# Connector_Sheet2.net
KiCad netlist of a schematic drawn in Altium Designer
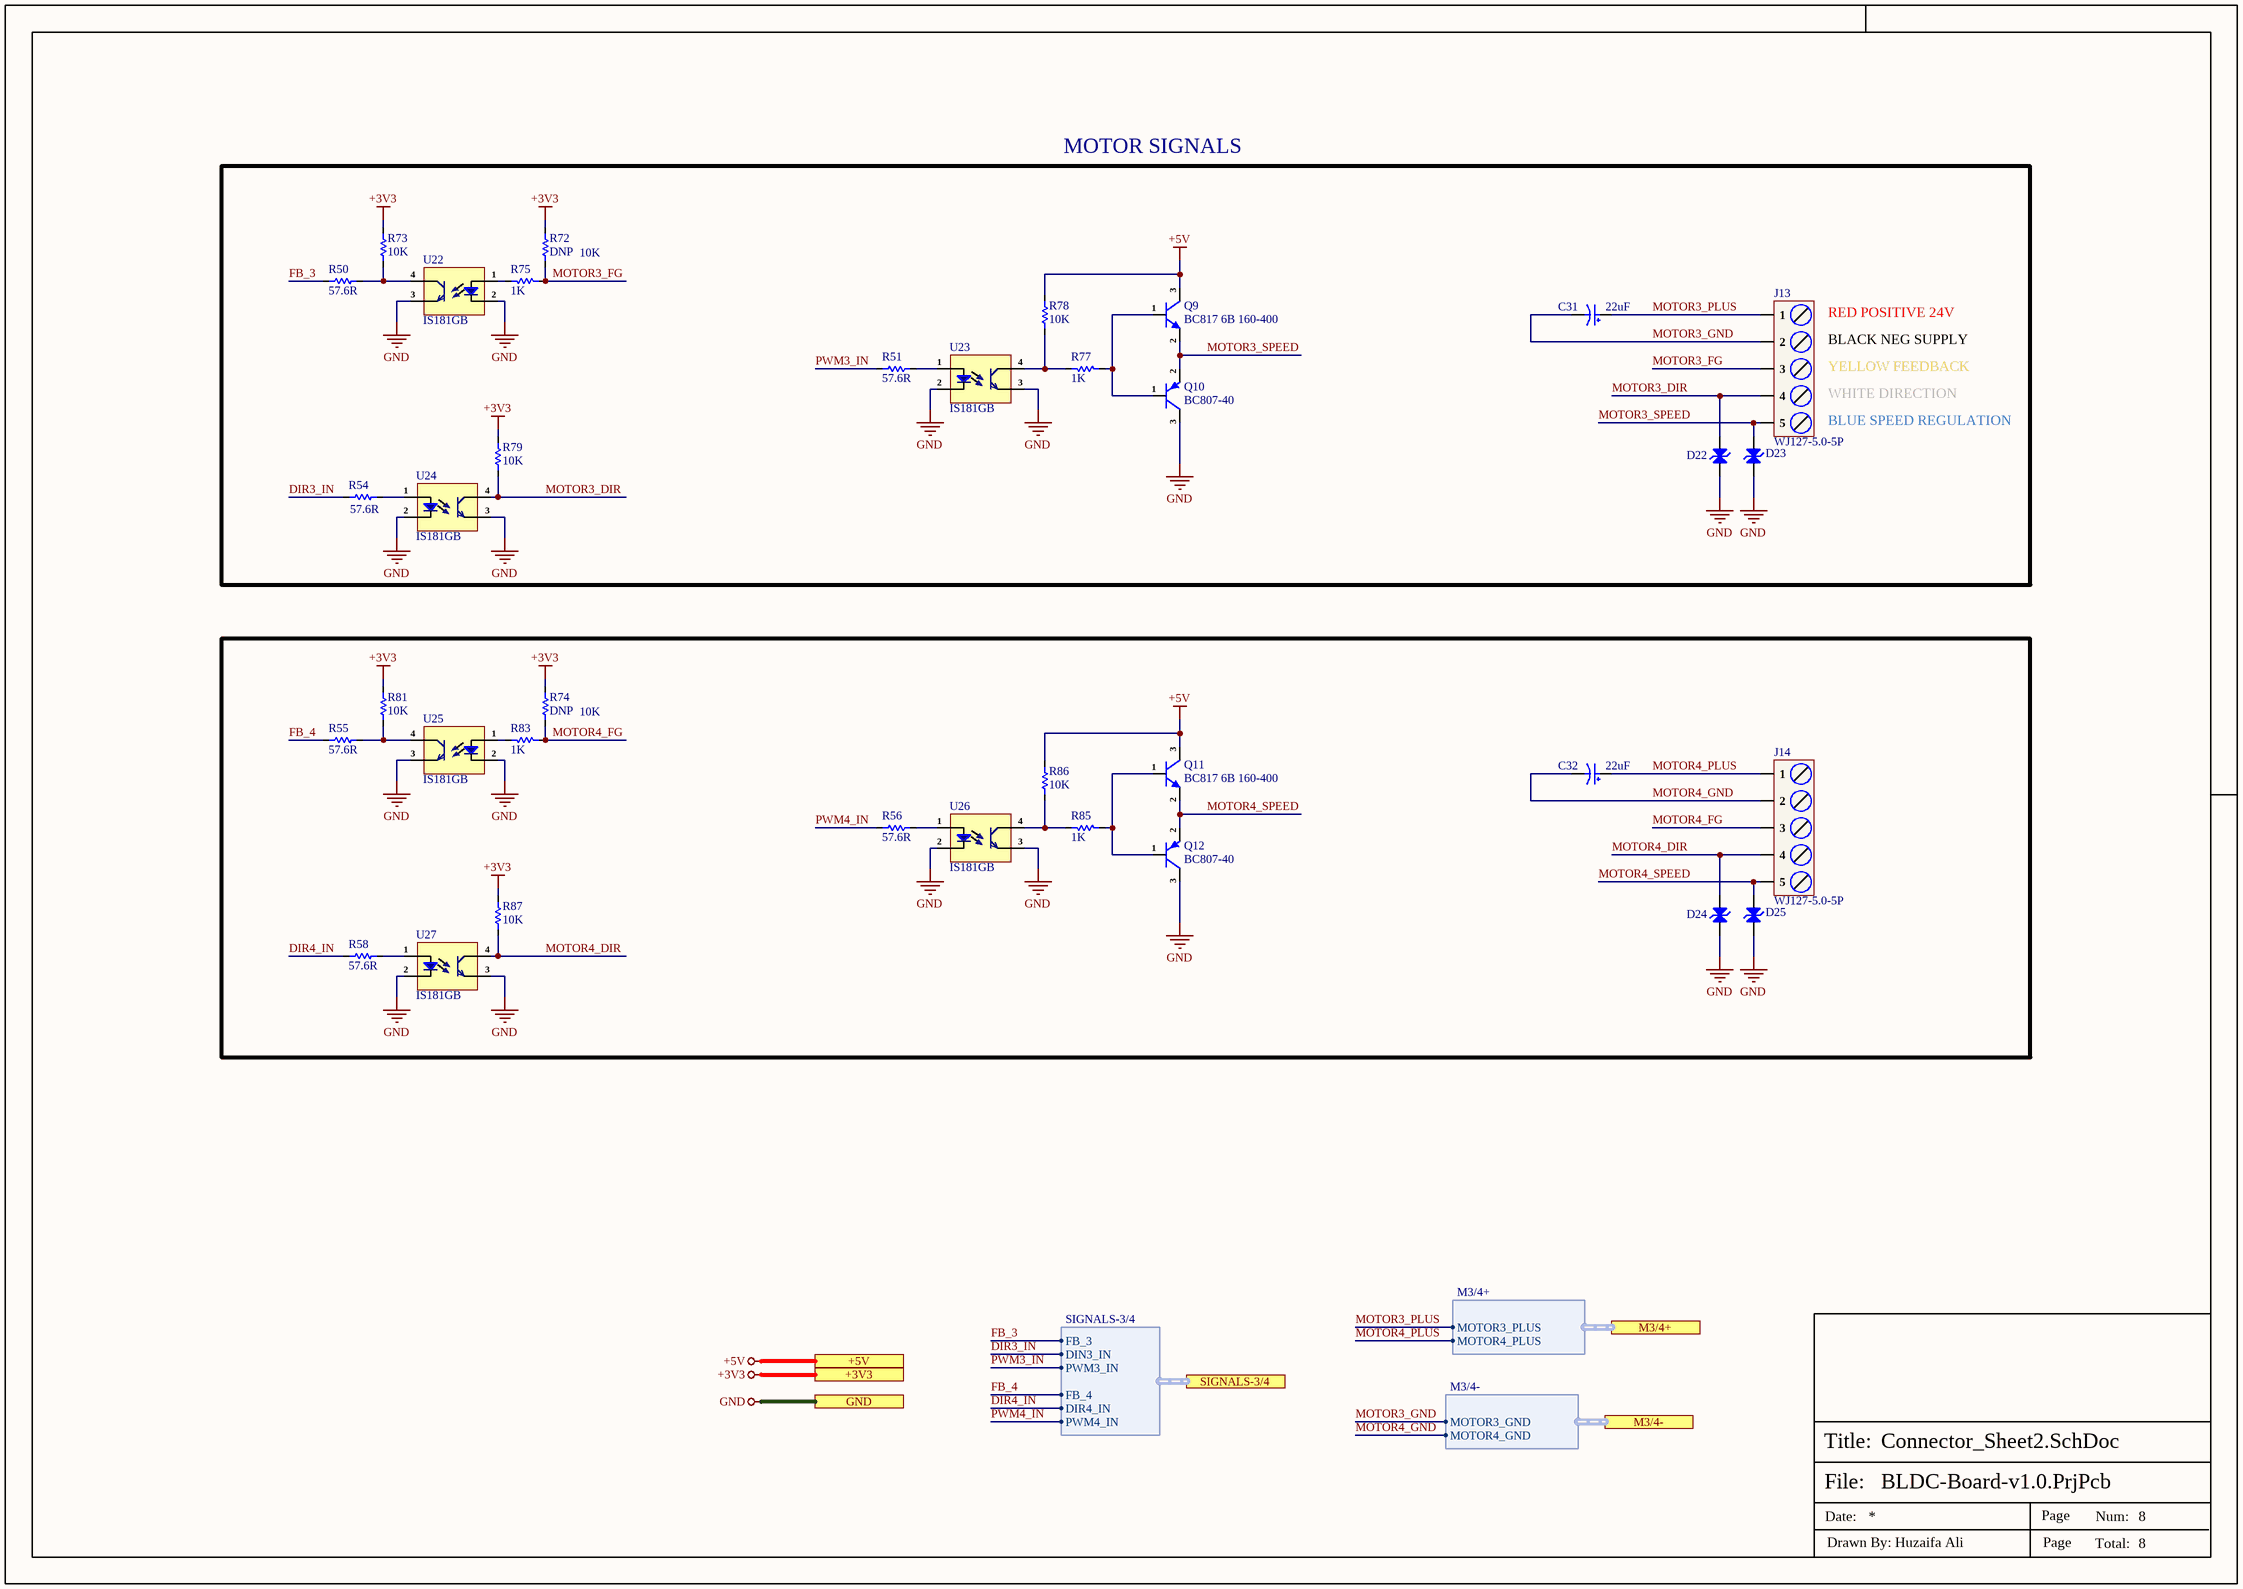
[diagram p0: Connector_Sheet2.SchDoc]

(export (version "E")
  (design (tool "Eeschema 10.0.6"))
  (components
    (comp (ref "C31")
      (value "22uF")
      (footprint "VKMD1652D220MV")
      (description "22uF 200V 320mA@100kHz ±20% SMD,D8xL16.5mm Aluminum Electrolytic Capacitors - SMD ROHS")
      (fields (field (name "MANUFACTURER") "Ymin") (field (name "MANUFACTURER PART NUMBER") "VKMD1652D220MV"))
      (libsource (lib "eSpark Libraries") (part "VKMD1652D220MV"))
    )
    (comp (ref "C32")
      (value "22uF")
      (footprint "VKMD1652D220MV")
      (description "22uF 200V 320mA@100kHz ±20% SMD,D8xL16.5mm Aluminum Electrolytic Capacitors - SMD ROHS")
      (fields (field (name "MANUFACTURER") "Ymin") (field (name "MANUFACTURER PART NUMBER") "VKMD1652D220MV"))
      (libsource (lib "eSpark Libraries") (part "VKMD1652D220MV"))
    )
    (comp (ref "D22")
      (value "ESD5B5.0ST1G")
      (footprint "SOD-523")
      (description "TVS DIODE 5VWM SOD523")
      (fields (field (name "MANUFACTURER") "ON Semiconductor") (field (name "LCSC PART NUMBER") "C93623"))
      (libsource (lib "eSpark Libraries") (part "ESD5B5.0ST1G"))
    )
    (comp (ref "D23")
      (value "ESD5B5.0ST1G")
      (footprint "SOD-523")
      (description "TVS DIODE 5VWM SOD523")
      (fields (field (name "MANUFACTURER") "ON Semiconductor") (field (name "LCSC PART NUMBER") "C93623"))
      (libsource (lib "eSpark Libraries") (part "ESD5B5.0ST1G"))
    )
    (comp (ref "D24")
      (value "ESD5B5.0ST1G")
      (footprint "SOD-523")
      (description "TVS DIODE 5VWM SOD523")
      (fields (field (name "MANUFACTURER") "ON Semiconductor") (field (name "LCSC PART NUMBER") "C93623"))
      (libsource (lib "eSpark Libraries") (part "ESD5B5.0ST1G"))
    )
    (comp (ref "D25")
      (value "ESD5B5.0ST1G")
      (footprint "SOD-523")
      (description "TVS DIODE 5VWM SOD523")
      (fields (field (name "MANUFACTURER") "ON Semiconductor") (field (name "LCSC PART NUMBER") "C93623"))
      (libsource (lib "eSpark Libraries") (part "ESD5B5.0ST1G"))
    )
    (comp (ref "J13")
      (value "WJ127-5.0-5P")
      (footprint "WJ127-5.0-5P")
      (description "1x5P -40℃~+105℃ 15A 250V Green 14~26 Straight pin 5mm 1.5 1 5 Plugin,P=5mm Screw terminal ROHS")
      (fields (field (name "MANUFACTURER") "Ningbo Kangnex Elec") (field (name "LCSC PART NUMBER") "C192780"))
      (libsource (lib "eSpark Libraries") (part "WJ127-5.0-5P"))
    )
    (comp (ref "J14")
      (value "WJ127-5.0-5P")
      (footprint "WJ127-5.0-5P")
      (description "1x5P -40℃~+105℃ 15A 250V Green 14~26 Straight pin 5mm 1.5 1 5 Plugin,P=5mm Screw terminal ROHS")
      (fields (field (name "MANUFACTURER") "Ningbo Kangnex Elec") (field (name "LCSC PART NUMBER") "C192780"))
      (libsource (lib "eSpark Libraries") (part "WJ127-5.0-5P"))
    )
    (comp (ref "Q9")
      (value "BC817 6B 160-400")
      (footprint "SOT-23")
      (description "45V 300mW 100@100mA,1V 500mA NPN SOT-23 Bipolar Transistors - BJT ROHS")
      (fields (field (name "MANUFACTURER") "DOWO") (field (name "LCSC PART NUMBER") "C371086"))
      (libsource (lib "eSpark Libraries") (part "BC817 6B 160-400"))
    )
    (comp (ref "Q10")
      (value "BC807-40")
      (footprint "SOT-23")
      (description "45V 310mW 250@100mA,1V 800mA SOT-23 Bipolar (BJT) ROHS")
      (fields (field (name "MANUFACTURER") "KEXIN") (field (name "LCSC PART NUMBER") "C489159"))
      (libsource (lib "eSpark Libraries") (part "BC807-40"))
    )
    (comp (ref "Q11")
      (value "BC817 6B 160-400")
      (footprint "SOT-23")
      (description "45V 300mW 100@100mA,1V 500mA NPN SOT-23 Bipolar Transistors - BJT ROHS")
      (fields (field (name "MANUFACTURER") "DOWO") (field (name "LCSC PART NUMBER") "C371086"))
      (libsource (lib "eSpark Libraries") (part "BC817 6B 160-400"))
    )
    (comp (ref "Q12")
      (value "BC807-40")
      (footprint "SOT-23")
      (description "45V 310mW 250@100mA,1V 800mA SOT-23 Bipolar (BJT) ROHS")
      (fields (field (name "MANUFACTURER") "KEXIN") (field (name "LCSC PART NUMBER") "C489159"))
      (libsource (lib "eSpark Libraries") (part "BC807-40"))
    )
    (comp (ref "R50")
      (value "57.6R")
      (footprint "Res-0402")
      (description "RES SMD 57.6 OHM 1% 1/10W 0402")
      (fields
        (field (name "MANUFACTURER") "Panasonic")
        (field (name "MANUFACTURER PART NUMBER") "ERJ-2RKF57R6X")
      )
      (libsource (lib "eSpark Libraries") (part "ERJ-2RKF57R6X"))
    )
    (comp (ref "R51")
      (value "57.6R")
      (footprint "Res-0402")
      (description "RES SMD 57.6 OHM 1% 1/10W 0402")
      (fields
        (field (name "MANUFACTURER") "Panasonic")
        (field (name "MANUFACTURER PART NUMBER") "ERJ-2RKF57R6X")
      )
      (libsource (lib "eSpark Libraries") (part "ERJ-2RKF57R6X"))
    )
    (comp (ref "R54")
      (value "57.6R")
      (footprint "Res-0402")
      (description "RES SMD 57.6 OHM 1% 1/10W 0402")
      (fields
        (field (name "MANUFACTURER") "Panasonic")
        (field (name "MANUFACTURER PART NUMBER") "ERJ-2RKF57R6X")
      )
      (libsource (lib "eSpark Libraries") (part "ERJ-2RKF57R6X"))
    )
    (comp (ref "R55")
      (value "57.6R")
      (footprint "Res-0402")
      (description "RES SMD 57.6 OHM 1% 1/10W 0402")
      (fields
        (field (name "MANUFACTURER") "Panasonic")
        (field (name "MANUFACTURER PART NUMBER") "ERJ-2RKF57R6X")
      )
      (libsource (lib "eSpark Libraries") (part "ERJ-2RKF57R6X"))
    )
    (comp (ref "R56")
      (value "57.6R")
      (footprint "Res-0402")
      (description "RES SMD 57.6 OHM 1% 1/10W 0402")
      (fields
        (field (name "MANUFACTURER") "Panasonic")
        (field (name "MANUFACTURER PART NUMBER") "ERJ-2RKF57R6X")
      )
      (libsource (lib "eSpark Libraries") (part "ERJ-2RKF57R6X"))
    )
    (comp (ref "R58")
      (value "57.6R")
      (footprint "Res-0402")
      (description "RES SMD 57.6 OHM 1% 1/10W 0402")
      (fields
        (field (name "MANUFACTURER") "Panasonic")
        (field (name "MANUFACTURER PART NUMBER") "ERJ-2RKF57R6X")
      )
      (libsource (lib "eSpark Libraries") (part "ERJ-2RKF57R6X"))
    )
    (comp (ref "R72")
      (value "DNP")
      (footprint "Res-0402")
      (description "RES 10K OHM 1% 1/16W 0402")
      (fields
        (field (name "MANUFACTURER") "Yageo")
        (field (name "MANUFACTURER PART NUMBER") "RC0402FR-0710KL")
      )
      (libsource (lib "eSpark Libraries") (part "RC0402FR-0710KL"))
    )
    (comp (ref "R73")
      (value "10K")
      (footprint "Res-0402")
      (description "RES 10K OHM 1% 1/16W 0402")
      (fields
        (field (name "MANUFACTURER") "Yageo")
        (field (name "MANUFACTURER PART NUMBER") "RC0402FR-0710KL")
      )
      (libsource (lib "eSpark Libraries") (part "RC0402FR-0710KL"))
    )
    (comp (ref "R74")
      (value "DNP")
      (footprint "Res-0402")
      (description "RES 10K OHM 1% 1/16W 0402")
      (fields
        (field (name "MANUFACTURER") "Yageo")
        (field (name "MANUFACTURER PART NUMBER") "RC0402FR-0710KL")
      )
      (libsource (lib "eSpark Libraries") (part "RC0402FR-0710KL"))
    )
    (comp (ref "R75")
      (value "1K")
      (footprint "Res-0402")
      (description "RES SMD 1K OHM 1% 1/5W 0402")
      (fields
        (field (name "MANUFACTURER") "Vishay Dale")
        (field (name "MANUFACTURER PART NUMBER") "CRCW04021K00FKEDHP")
      )
      (libsource (lib "eSpark Libraries") (part "CRCW04021K00FKEDHP"))
    )
    (comp (ref "R77")
      (value "1K")
      (footprint "Res-0402")
      (description "RES SMD 1K OHM 1% 1/5W 0402")
      (fields
        (field (name "MANUFACTURER") "Vishay Dale")
        (field (name "MANUFACTURER PART NUMBER") "CRCW04021K00FKEDHP")
      )
      (libsource (lib "eSpark Libraries") (part "CRCW04021K00FKEDHP"))
    )
    (comp (ref "R78")
      (value "10K")
      (footprint "Res-0402")
      (description "RES 10K OHM 1% 1/16W 0402")
      (fields
        (field (name "MANUFACTURER") "Yageo")
        (field (name "MANUFACTURER PART NUMBER") "RC0402FR-0710KL")
      )
      (libsource (lib "eSpark Libraries") (part "RC0402FR-0710KL"))
    )
    (comp (ref "R79")
      (value "10K")
      (footprint "Res-0402")
      (description "RES 10K OHM 1% 1/16W 0402")
      (fields
        (field (name "MANUFACTURER") "Yageo")
        (field (name "MANUFACTURER PART NUMBER") "RC0402FR-0710KL")
      )
      (libsource (lib "eSpark Libraries") (part "RC0402FR-0710KL"))
    )
    (comp (ref "R81")
      (value "10K")
      (footprint "Res-0402")
      (description "RES 10K OHM 1% 1/16W 0402")
      (fields
        (field (name "MANUFACTURER") "Yageo")
        (field (name "MANUFACTURER PART NUMBER") "RC0402FR-0710KL")
      )
      (libsource (lib "eSpark Libraries") (part "RC0402FR-0710KL"))
    )
    (comp (ref "R83")
      (value "1K")
      (footprint "Res-0402")
      (description "RES SMD 1K OHM 1% 1/5W 0402")
      (fields
        (field (name "MANUFACTURER") "Vishay Dale")
        (field (name "MANUFACTURER PART NUMBER") "CRCW04021K00FKEDHP")
      )
      (libsource (lib "eSpark Libraries") (part "CRCW04021K00FKEDHP"))
    )
    (comp (ref "R85")
      (value "1K")
      (footprint "Res-0402")
      (description "RES SMD 1K OHM 1% 1/5W 0402")
      (fields
        (field (name "MANUFACTURER") "Vishay Dale")
        (field (name "MANUFACTURER PART NUMBER") "CRCW04021K00FKEDHP")
      )
      (libsource (lib "eSpark Libraries") (part "CRCW04021K00FKEDHP"))
    )
    (comp (ref "R86")
      (value "10K")
      (footprint "Res-0402")
      (description "RES 10K OHM 1% 1/16W 0402")
      (fields
        (field (name "MANUFACTURER") "Yageo")
        (field (name "MANUFACTURER PART NUMBER") "RC0402FR-0710KL")
      )
      (libsource (lib "eSpark Libraries") (part "RC0402FR-0710KL"))
    )
    (comp (ref "R87")
      (value "10K")
      (footprint "Res-0402")
      (description "RES 10K OHM 1% 1/16W 0402")
      (fields
        (field (name "MANUFACTURER") "Yageo")
        (field (name "MANUFACTURER PART NUMBER") "RC0402FR-0710KL")
      )
      (libsource (lib "eSpark Libraries") (part "RC0402FR-0710KL"))
    )
    (comp (ref "U22")
      (value "IS181GB")
      (footprint "SOP-4_2.54")
      (description "Optoisolator Transistor Output 3750Vrms 1 Channel")
      (fields (field (name "MANUFACTURER") "Isocom") (field (name "LCSC PART NUMBER") "C84196"))
      (libsource (lib "eSpark Libraries") (part "IS181GB"))
    )
    (comp (ref "U23")
      (value "IS181GB")
      (footprint "SOP-4_2.54")
      (description "Optoisolator Transistor Output 3750Vrms 1 Channel")
      (fields (field (name "MANUFACTURER") "Isocom") (field (name "LCSC PART NUMBER") "C84196"))
      (libsource (lib "") (part "IS181GB_1"))
    )
    (comp (ref "U24")
      (value "IS181GB")
      (footprint "SOP-4_2.54")
      (description "Optoisolator Transistor Output 3750Vrms 1 Channel")
      (fields (field (name "MANUFACTURER") "Isocom") (field (name "LCSC PART NUMBER") "C84196"))
      (libsource (lib "") (part "IS181GB_1"))
    )
    (comp (ref "U25")
      (value "IS181GB")
      (footprint "SOP-4_2.54")
      (description "Optoisolator Transistor Output 3750Vrms 1 Channel")
      (fields (field (name "MANUFACTURER") "Isocom") (field (name "LCSC PART NUMBER") "C84196"))
      (libsource (lib "eSpark Libraries") (part "IS181GB"))
    )
    (comp (ref "U26")
      (value "IS181GB")
      (footprint "SOP-4_2.54")
      (description "Optoisolator Transistor Output 3750Vrms 1 Channel")
      (fields (field (name "MANUFACTURER") "Isocom") (field (name "LCSC PART NUMBER") "C84196"))
      (libsource (lib "") (part "IS181GB_1"))
    )
    (comp (ref "U27")
      (value "IS181GB")
      (footprint "SOP-4_2.54")
      (description "Optoisolator Transistor Output 3750Vrms 1 Channel")
      (fields (field (name "MANUFACTURER") "Isocom") (field (name "LCSC PART NUMBER") "C84196"))
      (libsource (lib "") (part "IS181GB_1"))
    )
  )
  (nets
    (net (code "4") (name "+3V3") (class "Default")
      (node (ref "R72") (pin "2") (pinfunction "2_2") (pintype "passive"))
      (node (ref "R73") (pin "2") (pinfunction "2_2") (pintype "passive"))
      (node (ref "R74") (pin "2") (pinfunction "2_2") (pintype "passive"))
      (node (ref "R79") (pin "2") (pinfunction "2_2") (pintype "passive"))
      (node (ref "R81") (pin "2") (pinfunction "2_2") (pintype "passive"))
      (node (ref "R87") (pin "2") (pinfunction "2_2") (pintype "passive"))
    )
    (net (code "5") (name "+5V") (class "Default")
      (node (ref "Q11") (pin "3") (pinfunction "C_3") (pintype "passive"))
      (node (ref "Q9") (pin "3") (pinfunction "C_3") (pintype "passive"))
      (node (ref "R78") (pin "1") (pinfunction "1_1") (pintype "passive"))
      (node (ref "R86") (pin "1") (pinfunction "1_1") (pintype "passive"))
    )
    (net (code "6") (name "/DIR3_IN") (class "Default")
      (node (ref "R54") (pin "1") (pinfunction "1_1") (pintype "passive"))
    )
    (net (code "7") (name "/DIR4_IN") (class "Default")
      (node (ref "R58") (pin "1") (pinfunction "1_1") (pintype "passive"))
    )
    (net (code "8") (name "/FB_3") (class "Default")
      (node (ref "R50") (pin "1") (pinfunction "1_1") (pintype "passive"))
    )
    (net (code "9") (name "/FB_4") (class "Default")
      (node (ref "R55") (pin "1") (pinfunction "1_1") (pintype "passive"))
    )
    (net (code "10") (name "/MOTOR3_DIR") (class "Default")
      (node (ref "D22") (pin "2") (pinfunction "A_2") (pintype "passive"))
      (node (ref "J13") (pin "4") (pinfunction "4_4") (pintype "passive"))
      (node (ref "R79") (pin "1") (pinfunction "1_1") (pintype "passive"))
      (node (ref "U24") (pin "4") (pinfunction "C_4") (pintype "passive"))
    )
    (net (code "11") (name "/MOTOR3_FG") (class "Default")
      (node (ref "J13") (pin "3") (pinfunction "3_3") (pintype "passive"))
      (node (ref "R72") (pin "1") (pinfunction "1_1") (pintype "passive"))
      (node (ref "R75") (pin "1") (pinfunction "1_1") (pintype "passive"))
    )
    (net (code "12") (name "/MOTOR3_GND") (class "Default")
      (node (ref "C31") (pin "2") (pintype "passive"))
      (node (ref "J13") (pin "2") (pinfunction "2_2") (pintype "passive"))
    )
    (net (code "13") (name "/MOTOR3_PLUS") (class "Default")
      (node (ref "C31") (pin "1") (pintype "passive"))
      (node (ref "J13") (pin "1") (pinfunction "1_1") (pintype "passive"))
    )
    (net (code "14") (name "/MOTOR3_SPEED") (class "Default")
      (node (ref "D23") (pin "2") (pinfunction "A_2") (pintype "passive"))
      (node (ref "J13") (pin "5") (pinfunction "5_5") (pintype "passive"))
      (node (ref "Q10") (pin "2") (pinfunction "E_2") (pintype "passive"))
      (node (ref "Q9") (pin "2") (pinfunction "E_2") (pintype "passive"))
    )
    (net (code "15") (name "/MOTOR4_DIR") (class "Default")
      (node (ref "D24") (pin "2") (pinfunction "A_2") (pintype "passive"))
      (node (ref "J14") (pin "4") (pinfunction "4_4") (pintype "passive"))
      (node (ref "R87") (pin "1") (pinfunction "1_1") (pintype "passive"))
      (node (ref "U27") (pin "4") (pinfunction "C_4") (pintype "passive"))
    )
    (net (code "16") (name "/MOTOR4_FG") (class "Default")
      (node (ref "J14") (pin "3") (pinfunction "3_3") (pintype "passive"))
      (node (ref "R74") (pin "1") (pinfunction "1_1") (pintype "passive"))
      (node (ref "R83") (pin "1") (pinfunction "1_1") (pintype "passive"))
    )
    (net (code "17") (name "/MOTOR4_GND") (class "Default")
      (node (ref "C32") (pin "2") (pintype "passive"))
      (node (ref "J14") (pin "2") (pinfunction "2_2") (pintype "passive"))
    )
    (net (code "18") (name "/MOTOR4_PLUS") (class "Default")
      (node (ref "C32") (pin "1") (pintype "passive"))
      (node (ref "J14") (pin "1") (pinfunction "1_1") (pintype "passive"))
    )
    (net (code "19") (name "/MOTOR4_SPEED") (class "Default")
      (node (ref "D25") (pin "2") (pinfunction "A_2") (pintype "passive"))
      (node (ref "J14") (pin "5") (pinfunction "5_5") (pintype "passive"))
      (node (ref "Q11") (pin "2") (pinfunction "E_2") (pintype "passive"))
      (node (ref "Q12") (pin "2") (pinfunction "E_2") (pintype "passive"))
    )
    (net (code "20") (name "/PWM3_IN") (class "Default")
      (node (ref "R51") (pin "1") (pinfunction "1_1") (pintype "passive"))
    )
    (net (code "21") (name "/PWM4_IN") (class "Default")
      (node (ref "R56") (pin "1") (pinfunction "1_1") (pintype "passive"))
    )
    (net (code "25") (name "GND") (class "Default")
      (node (ref "D22") (pin "1") (pinfunction "A_1") (pintype "passive"))
      (node (ref "D23") (pin "1") (pinfunction "A_1") (pintype "passive"))
      (node (ref "D24") (pin "1") (pinfunction "A_1") (pintype "passive"))
      (node (ref "D25") (pin "1") (pinfunction "A_1") (pintype "passive"))
      (node (ref "Q10") (pin "3") (pinfunction "C_3") (pintype "passive"))
      (node (ref "Q12") (pin "3") (pinfunction "C_3") (pintype "passive"))
      (node (ref "U22") (pin "2") (pinfunction "Ca_2") (pintype "passive"))
      (node (ref "U22") (pin "3") (pinfunction "E_3") (pintype "passive"))
      (node (ref "U23") (pin "2") (pinfunction "Ca_2") (pintype "passive"))
      (node (ref "U23") (pin "3") (pinfunction "E_3") (pintype "passive"))
      (node (ref "U24") (pin "2") (pinfunction "Ca_2") (pintype "passive"))
      (node (ref "U24") (pin "3") (pinfunction "E_3") (pintype "passive"))
      (node (ref "U25") (pin "2") (pinfunction "Ca_2") (pintype "passive"))
      (node (ref "U25") (pin "3") (pinfunction "E_3") (pintype "passive"))
      (node (ref "U26") (pin "2") (pinfunction "Ca_2") (pintype "passive"))
      (node (ref "U26") (pin "3") (pinfunction "E_3") (pintype "passive"))
      (node (ref "U27") (pin "2") (pinfunction "Ca_2") (pintype "passive"))
      (node (ref "U27") (pin "3") (pinfunction "E_3") (pintype "passive"))
    )
    (net (code "26") (name "Net-(Q10-B)") (class "Default")
      (node (ref "Q10") (pin "1") (pinfunction "B_1") (pintype "passive"))
      (node (ref "Q9") (pin "1") (pinfunction "B_1") (pintype "passive"))
      (node (ref "R77") (pin "1") (pinfunction "1_1") (pintype "passive"))
    )
    (net (code "27") (name "Net-(Q11-B)") (class "Default")
      (node (ref "Q11") (pin "1") (pinfunction "B_1") (pintype "passive"))
      (node (ref "Q12") (pin "1") (pinfunction "B_1") (pintype "passive"))
      (node (ref "R85") (pin "1") (pinfunction "1_1") (pintype "passive"))
    )
    (net (code "28") (name "Net-(U22-An)") (class "Default")
      (node (ref "R75") (pin "2") (pinfunction "2_2") (pintype "passive"))
      (node (ref "U22") (pin "1") (pinfunction "An_1") (pintype "passive"))
    )
    (net (code "29") (name "Net-(U22-C)") (class "Default")
      (node (ref "R50") (pin "2") (pinfunction "2_2") (pintype "passive"))
      (node (ref "R73") (pin "1") (pinfunction "1_1") (pintype "passive"))
      (node (ref "U22") (pin "4") (pinfunction "C_4") (pintype "passive"))
    )
    (net (code "30") (name "Net-(U23-An)") (class "Default")
      (node (ref "R51") (pin "2") (pinfunction "2_2") (pintype "passive"))
      (node (ref "U23") (pin "1") (pinfunction "An_1") (pintype "passive"))
    )
    (net (code "31") (name "Net-(U23-C)") (class "Default")
      (node (ref "R77") (pin "2") (pinfunction "2_2") (pintype "passive"))
      (node (ref "R78") (pin "2") (pinfunction "2_2") (pintype "passive"))
      (node (ref "U23") (pin "4") (pinfunction "C_4") (pintype "passive"))
    )
    (net (code "32") (name "Net-(U24-An)") (class "Default")
      (node (ref "R54") (pin "2") (pinfunction "2_2") (pintype "passive"))
      (node (ref "U24") (pin "1") (pinfunction "An_1") (pintype "passive"))
    )
    (net (code "33") (name "Net-(U25-An)") (class "Default")
      (node (ref "R83") (pin "2") (pinfunction "2_2") (pintype "passive"))
      (node (ref "U25") (pin "1") (pinfunction "An_1") (pintype "passive"))
    )
    (net (code "34") (name "Net-(U25-C)") (class "Default")
      (node (ref "R55") (pin "2") (pinfunction "2_2") (pintype "passive"))
      (node (ref "R81") (pin "1") (pinfunction "1_1") (pintype "passive"))
      (node (ref "U25") (pin "4") (pinfunction "C_4") (pintype "passive"))
    )
    (net (code "35") (name "Net-(U26-An)") (class "Default")
      (node (ref "R56") (pin "2") (pinfunction "2_2") (pintype "passive"))
      (node (ref "U26") (pin "1") (pinfunction "An_1") (pintype "passive"))
    )
    (net (code "36") (name "Net-(U26-C)") (class "Default")
      (node (ref "R85") (pin "2") (pinfunction "2_2") (pintype "passive"))
      (node (ref "R86") (pin "2") (pinfunction "2_2") (pintype "passive"))
      (node (ref "U26") (pin "4") (pinfunction "C_4") (pintype "passive"))
    )
    (net (code "37") (name "Net-(U27-An)") (class "Default")
      (node (ref "R58") (pin "2") (pinfunction "2_2") (pintype "passive"))
      (node (ref "U27") (pin "1") (pinfunction "An_1") (pintype "passive"))
    )
  )
)
